# MAX96724_PINOUT.net
KiCad netlist of a schematic drawn in Altium Designer
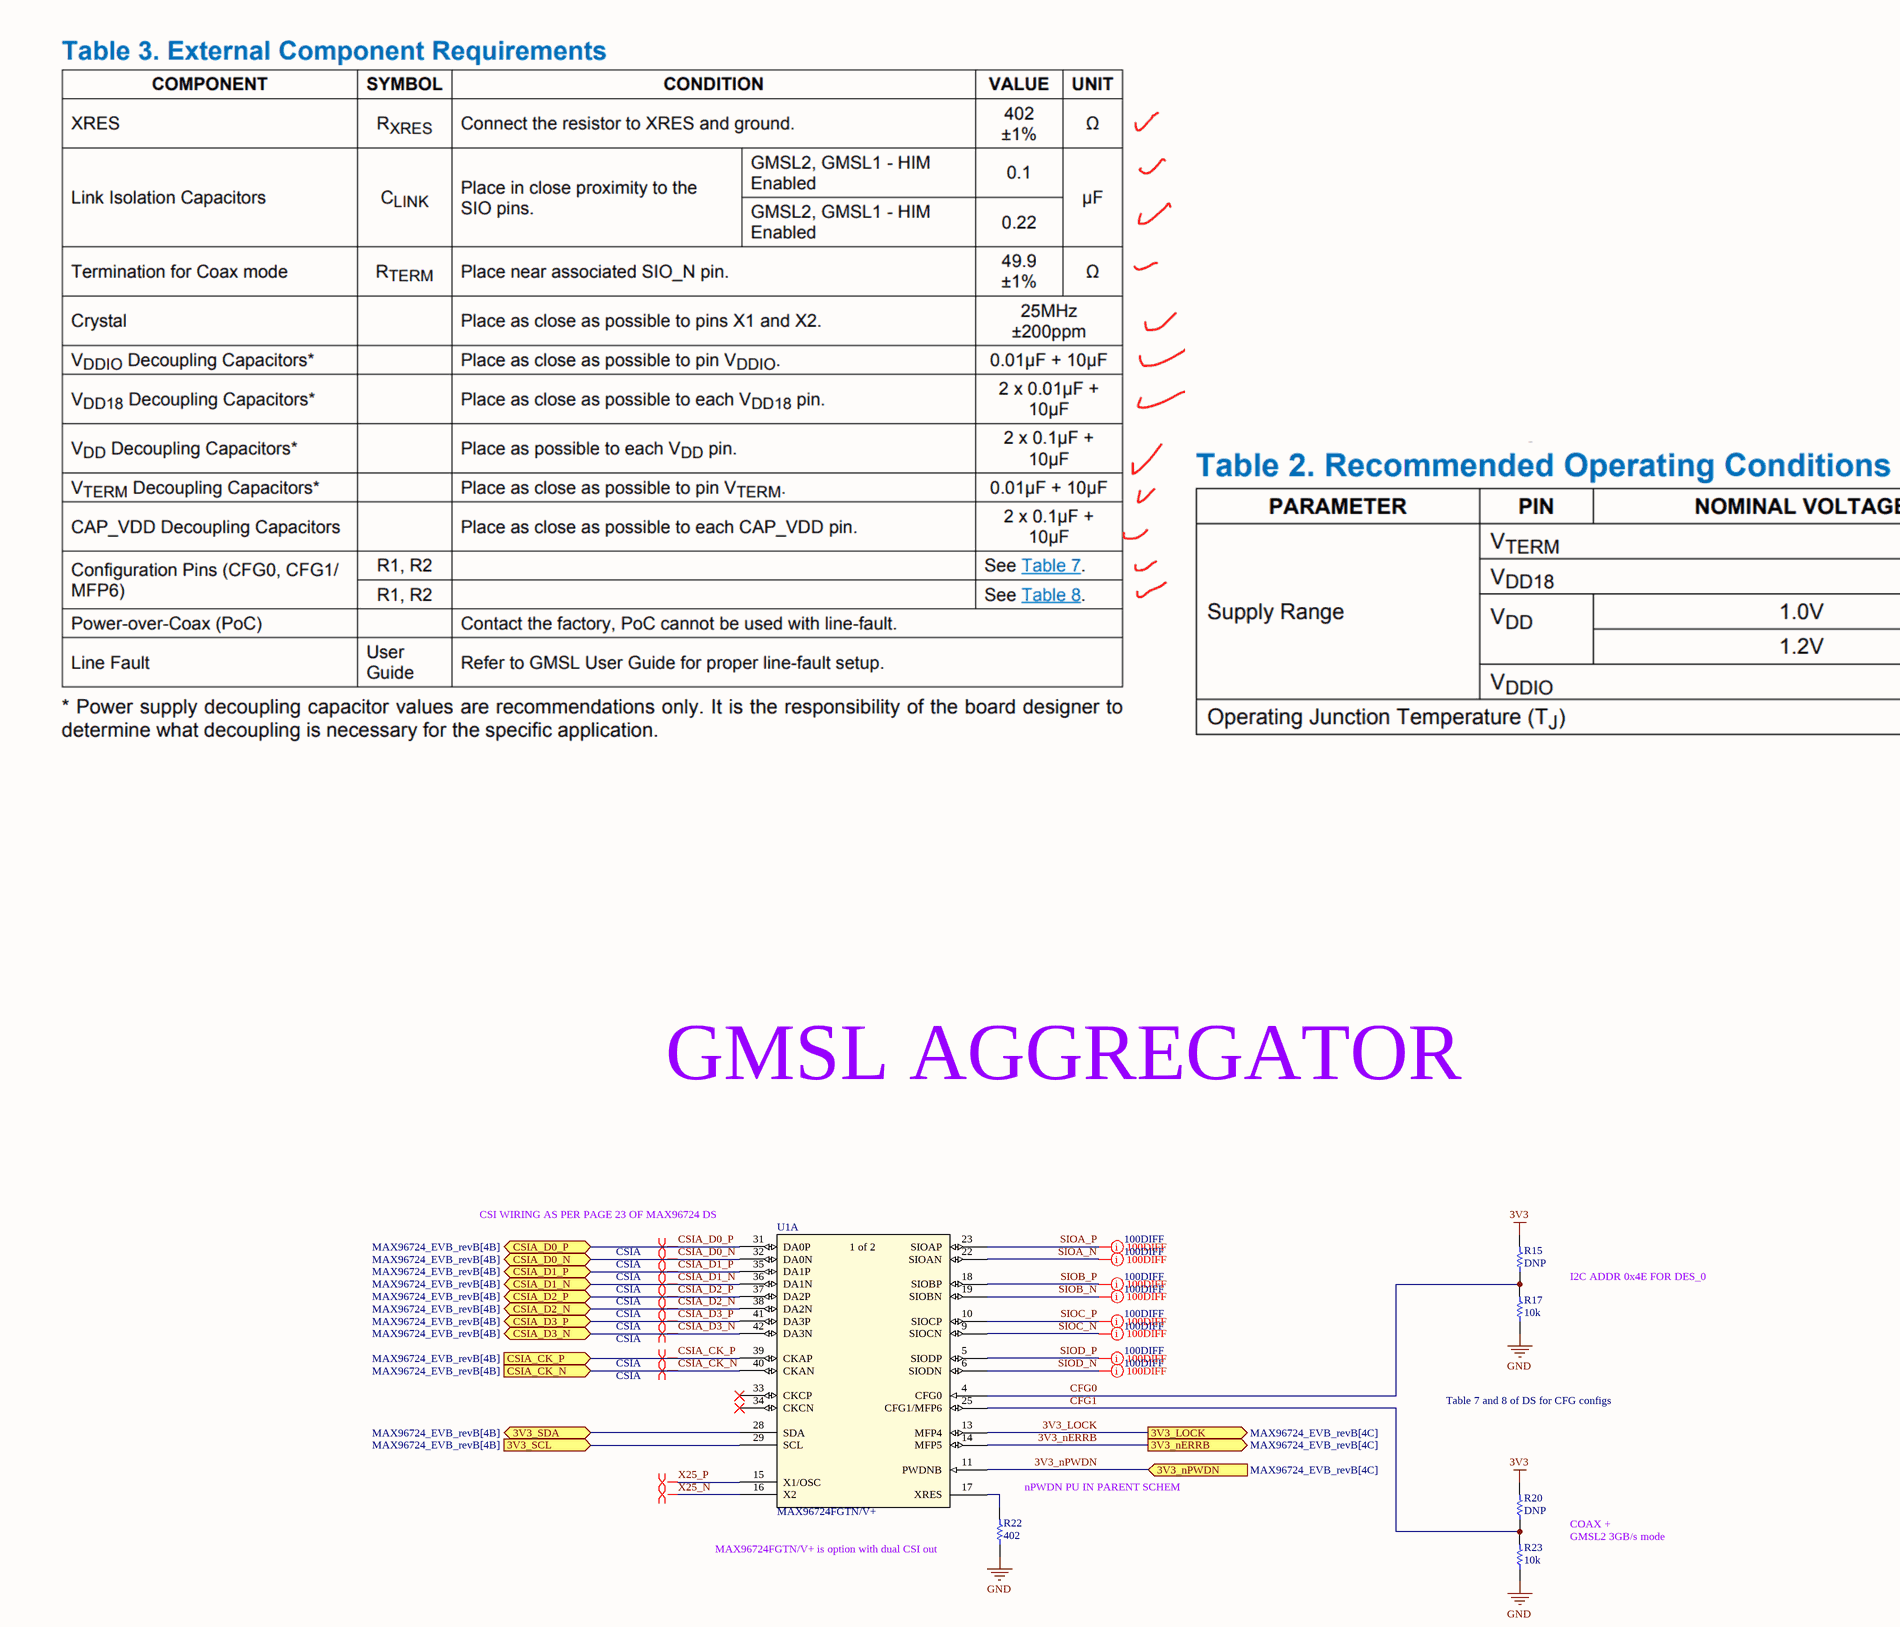
[diagram p0: MAX96724_PINOUT.SchDoc, top left]
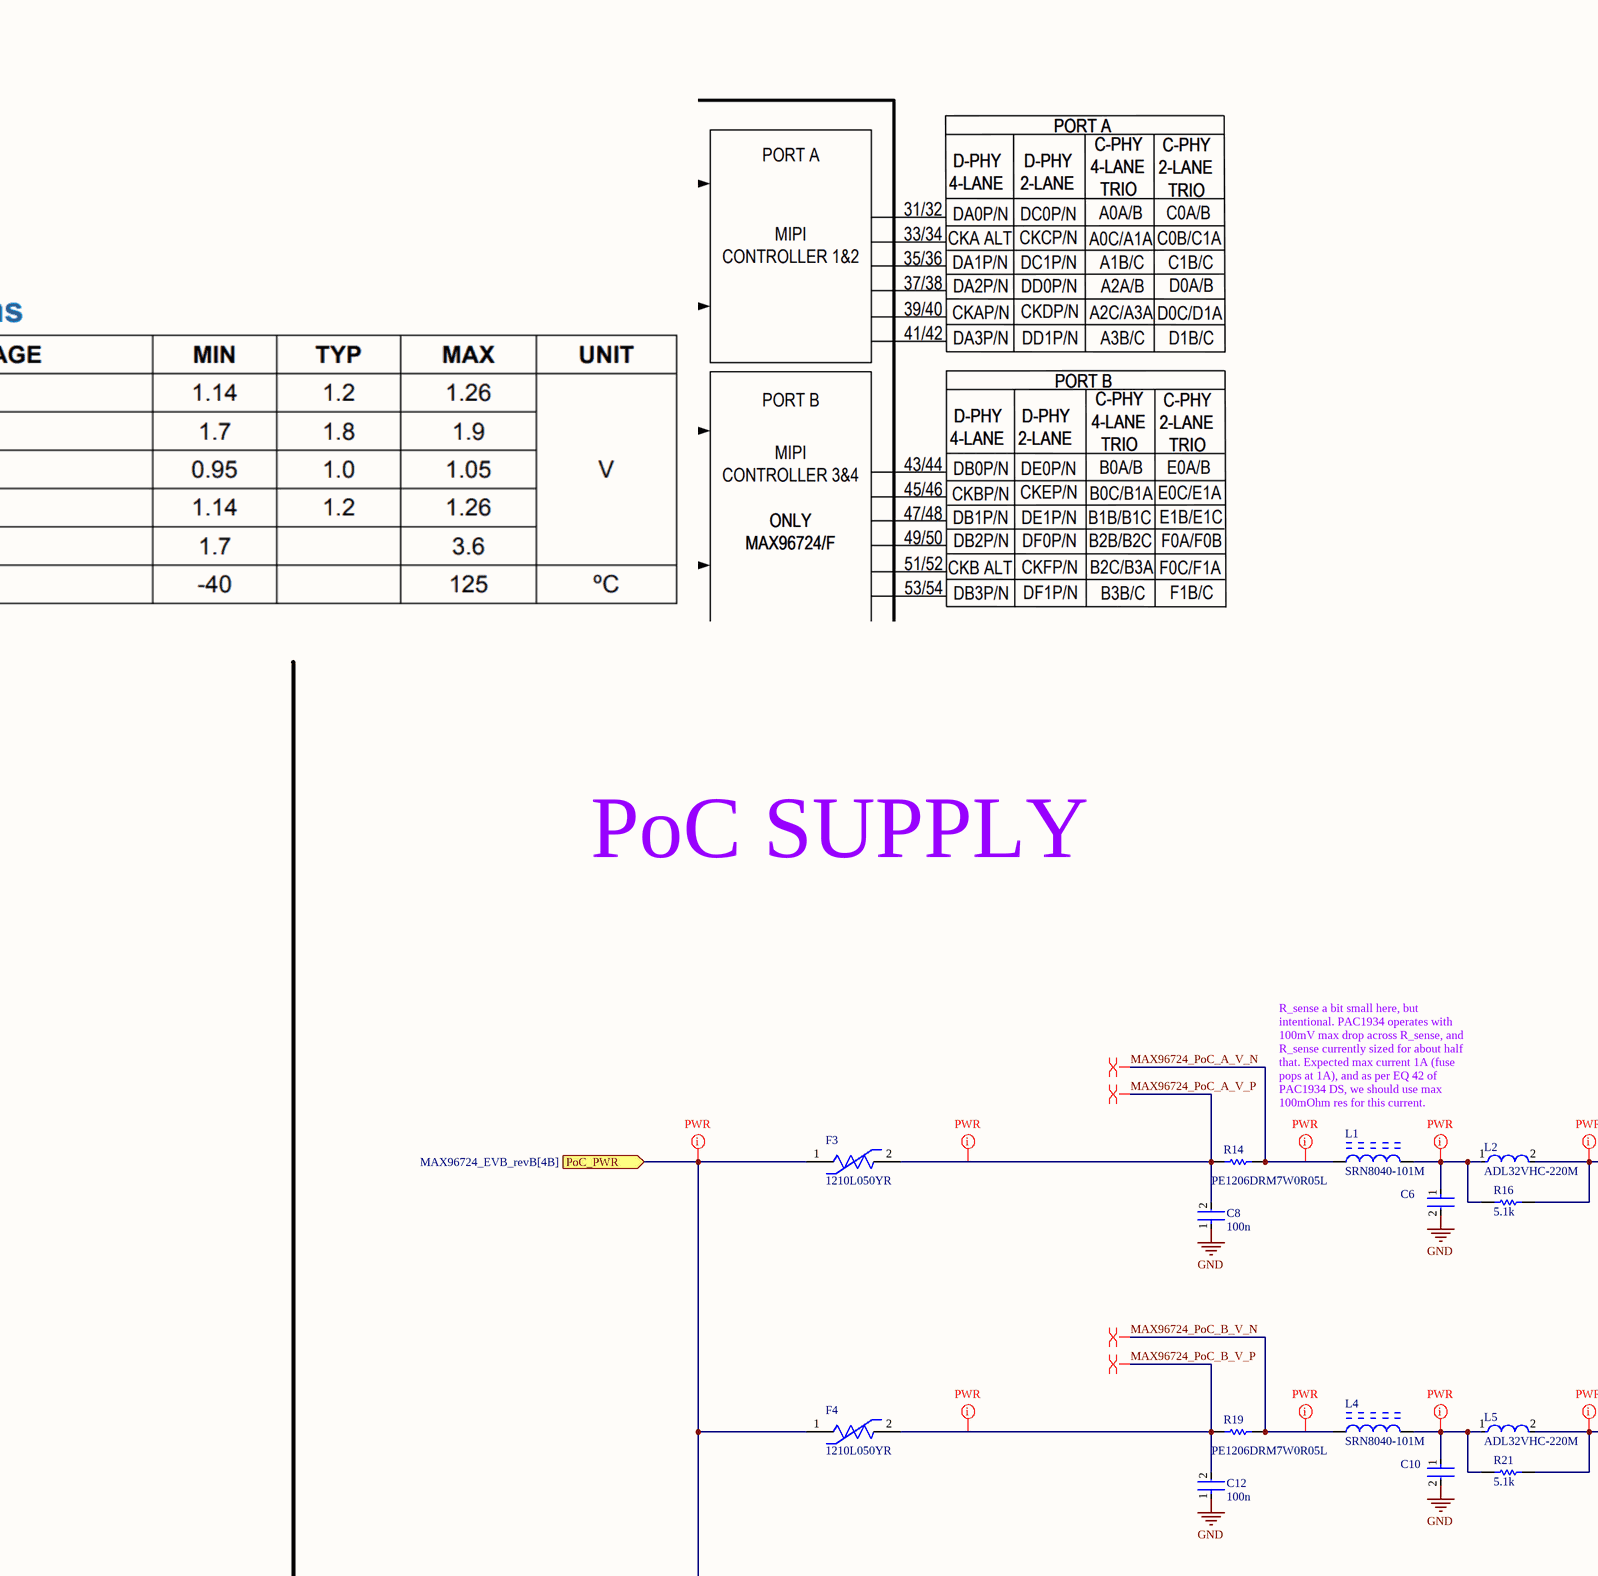
[diagram p1: MAX96724_PINOUT.SchDoc, top middle]
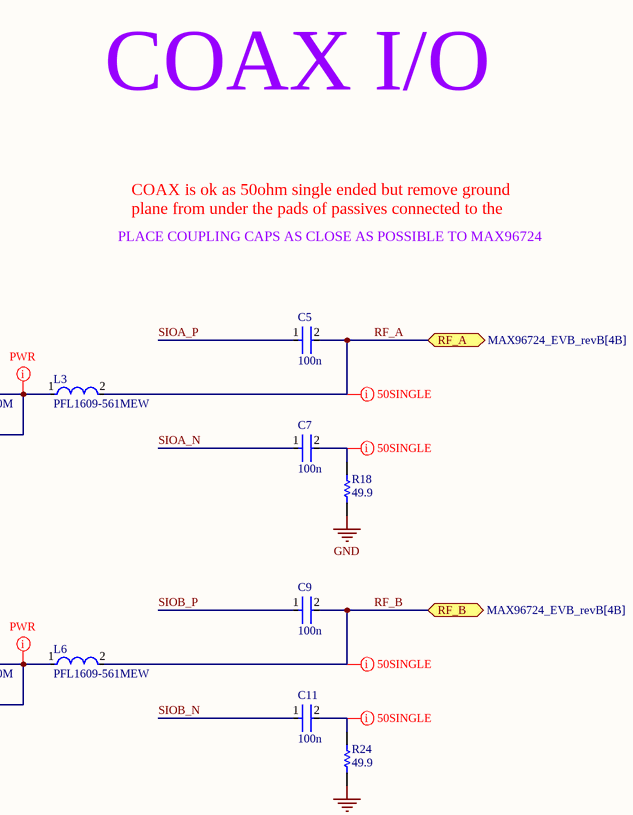
[diagram p2: MAX96724_PINOUT.SchDoc, top right]
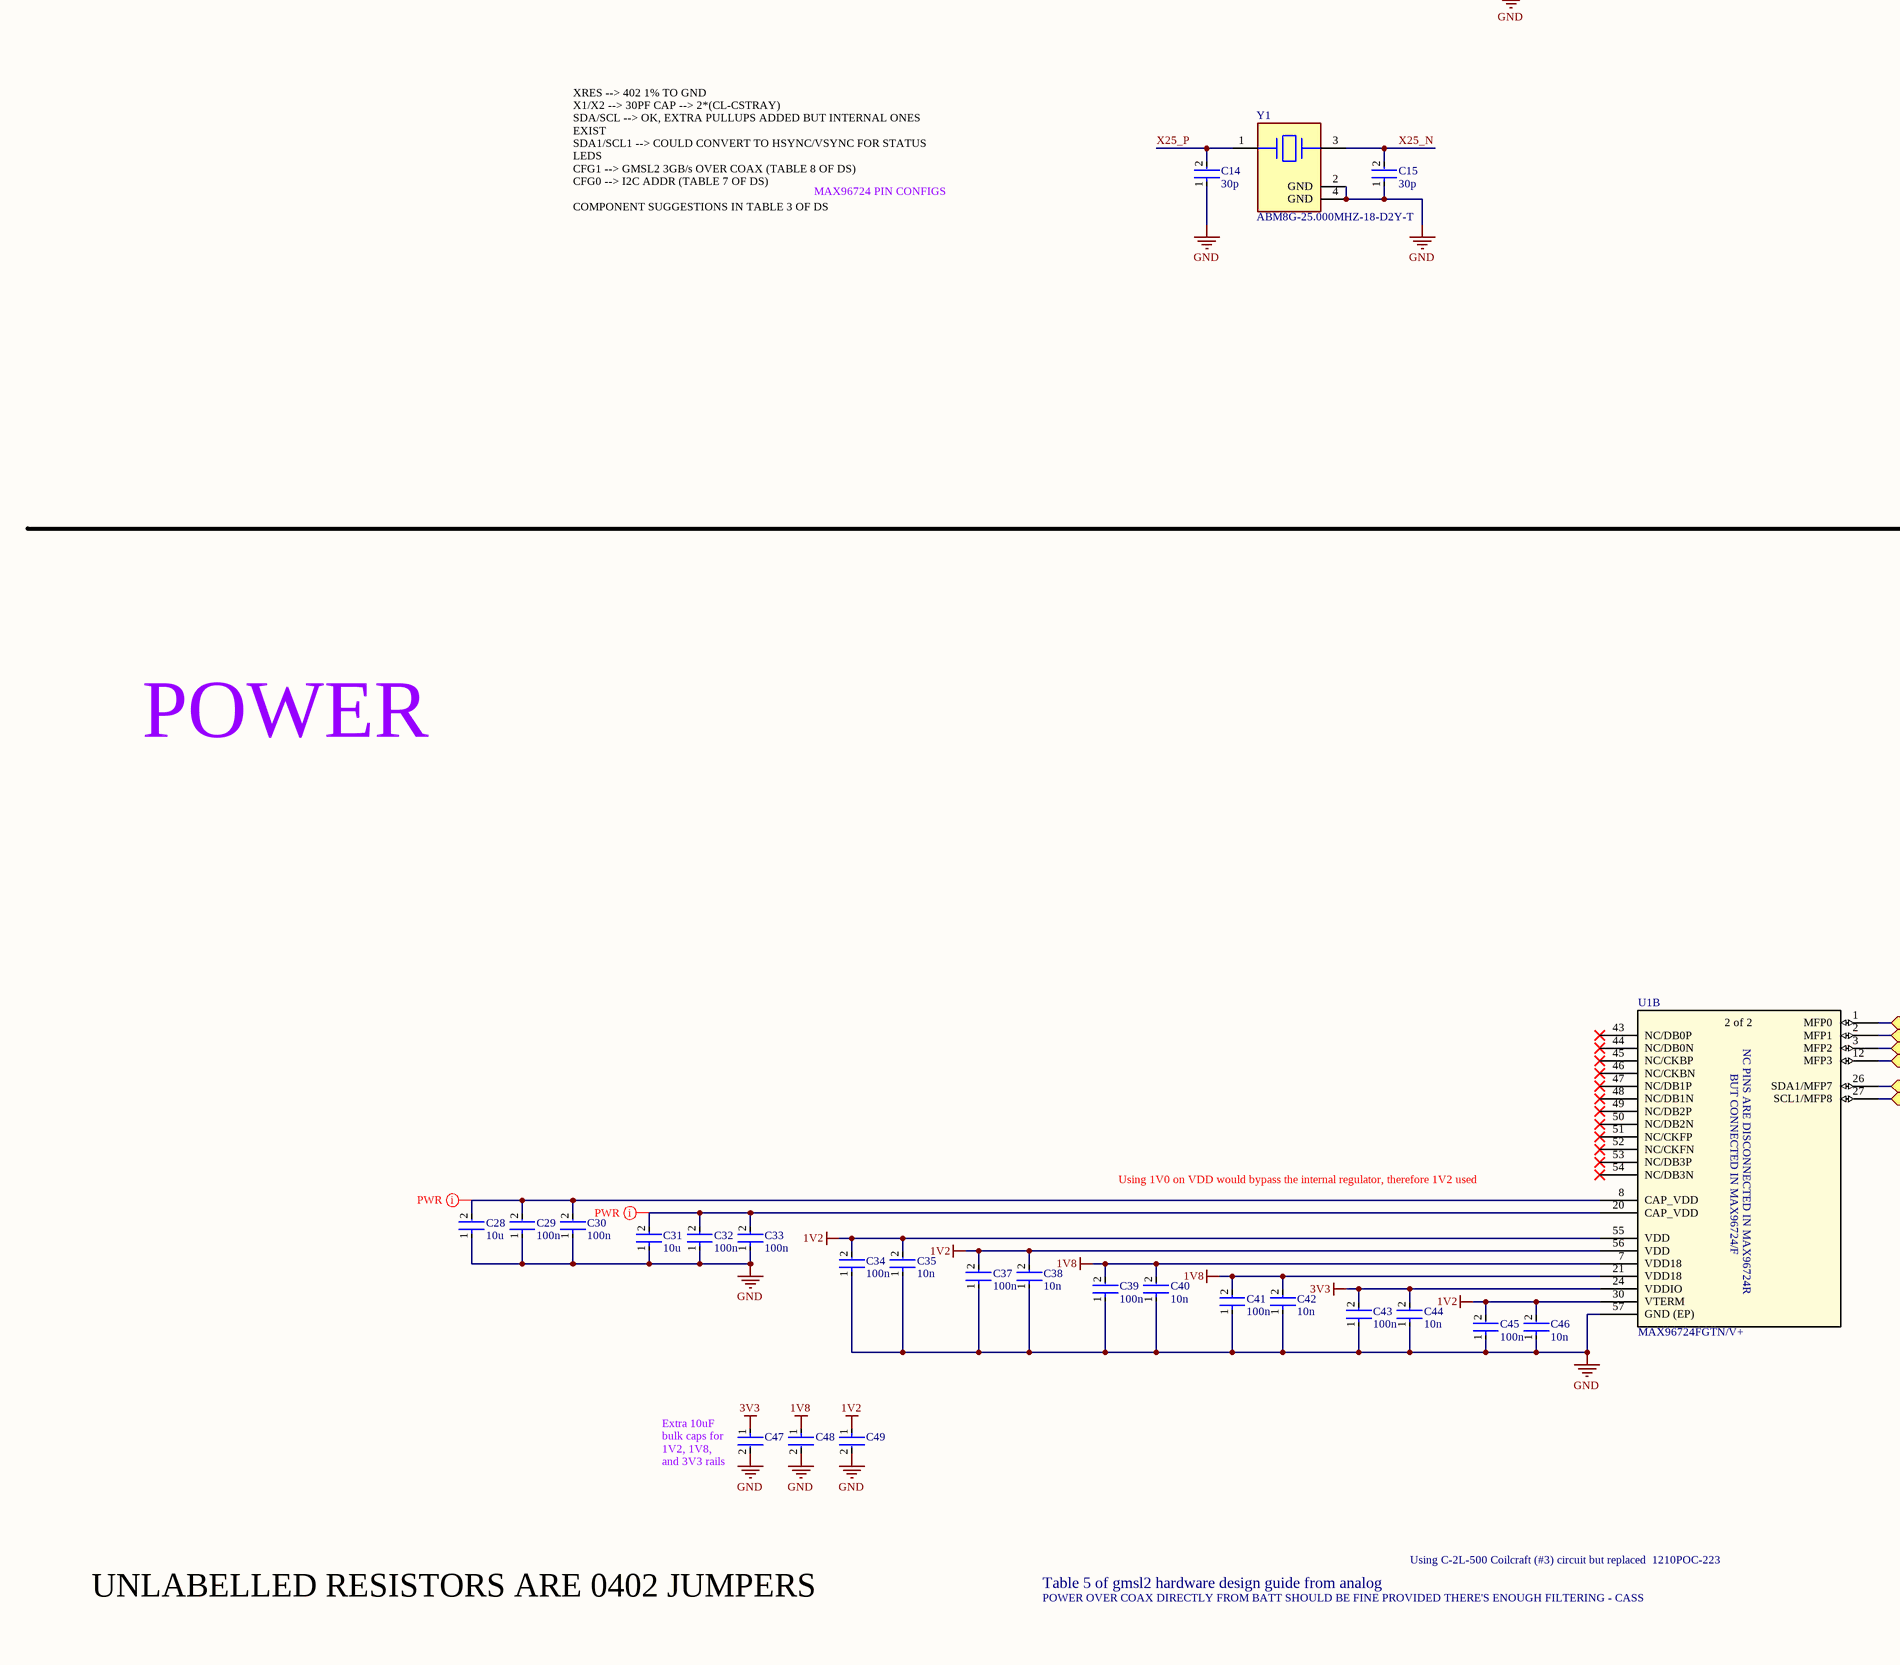
[diagram p3: MAX96724_PINOUT.SchDoc, bottom left]
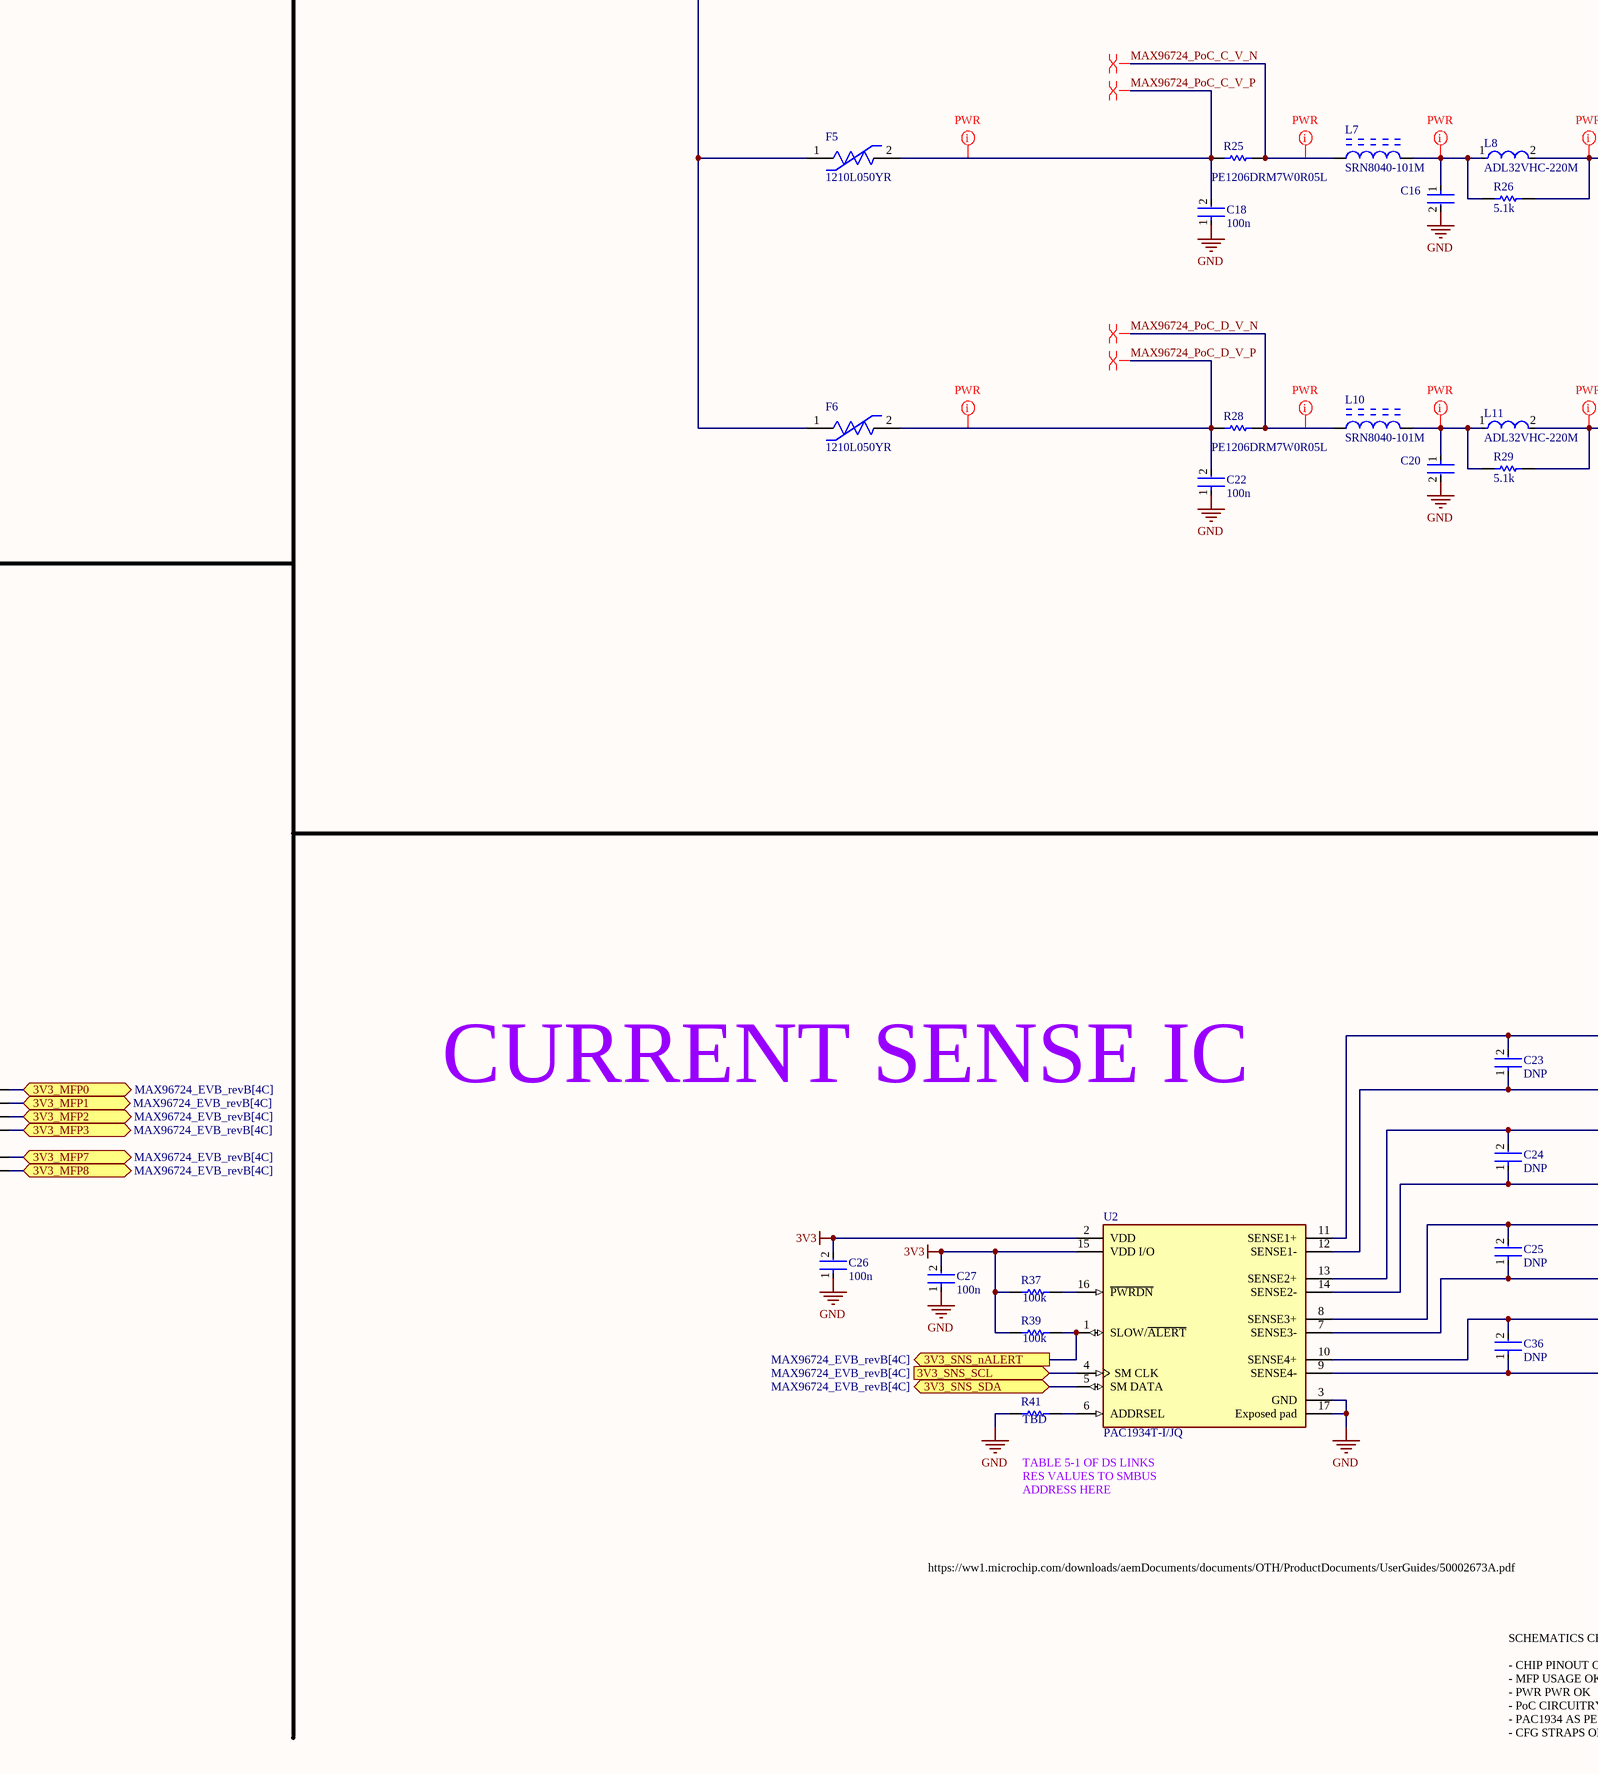
[diagram p4: MAX96724_PINOUT.SchDoc, bottom middle]
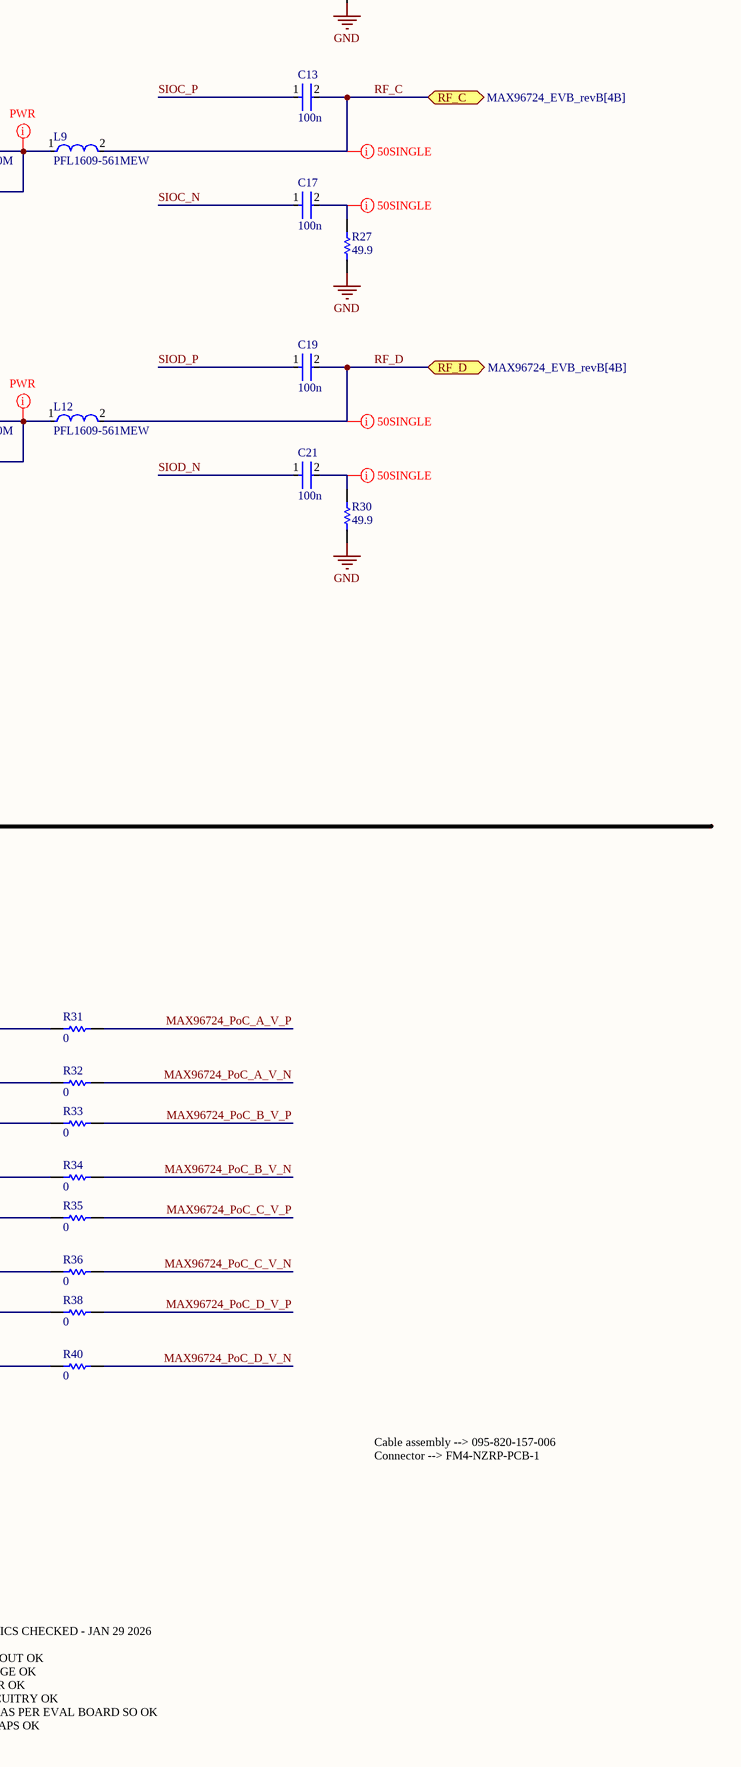
[diagram p5: MAX96724_PINOUT.SchDoc, bottom right]

(export (version "E")
  (design (tool "Eeschema 10.0.6"))
  (components
    (comp (ref "C5")
      (value "100n")
      (footprint "FP-0402-L_1_0_0_05-W_0_5-IPC_A")
      (description "LARGE PADS, 0402 CAP, CHANGE COMMENT TO MATCH REAL P/N")
      (libsource (lib "Space Concordia") (part "b4654b650e69147ec39a6b967a45e02"))
    )
    (comp (ref "C6")
      (value "GRM21BR61E226ME44L")
      (footprint "FP-GRM21B-0_2-e0_2_0_7-IPC_B")
      (description "Chip Multilayer Ceramic Capacitors for General Purpose, 0805, 22uF, X5R, 15%, 20%, 25V")
      (fields (field (name "TOLERANCE") "20%") (field (name "VOLTAGE") "25V"))
      (libsource (lib "Altium Content Vault") (part "b4654b650e69147ec39a6b967a45e02"))
    )
    (comp (ref "C7")
      (value "100n")
      (footprint "FP-0402-L_1_0_0_05-W_0_5-IPC_A")
      (description "LARGE PADS, 0402 CAP, CHANGE COMMENT TO MATCH REAL P/N")
      (libsource (lib "Space Concordia") (part "b4654b650e69147ec39a6b967a45e02"))
    )
    (comp (ref "C8")
      (value "100n")
      (footprint "FP-0402-L_1_0_0_05-W_0_5-IPC_A")
      (description "LARGE PADS, 0402 CAP, CHANGE COMMENT TO MATCH REAL P/N")
      (libsource (lib "Space Concordia") (part "b4654b650e69147ec39a6b967a45e02"))
    )
    (comp (ref "C9")
      (value "100n")
      (footprint "FP-0402-L_1_0_0_05-W_0_5-IPC_A")
      (description "LARGE PADS, 0402 CAP, CHANGE COMMENT TO MATCH REAL P/N")
      (libsource (lib "Space Concordia") (part "b4654b650e69147ec39a6b967a45e02"))
    )
    (comp (ref "C10")
      (value "GRM21BR61E226ME44L")
      (footprint "FP-GRM21B-0_2-e0_2_0_7-IPC_B")
      (description "Chip Multilayer Ceramic Capacitors for General Purpose, 0805, 22uF, X5R, 15%, 20%, 25V")
      (fields (field (name "TOLERANCE") "20%") (field (name "VOLTAGE") "25V"))
      (libsource (lib "Altium Content Vault") (part "b4654b650e69147ec39a6b967a45e02"))
    )
    (comp (ref "C11")
      (value "100n")
      (footprint "FP-0402-L_1_0_0_05-W_0_5-IPC_A")
      (description "LARGE PADS, 0402 CAP, CHANGE COMMENT TO MATCH REAL P/N")
      (libsource (lib "Space Concordia") (part "b4654b650e69147ec39a6b967a45e02"))
    )
    (comp (ref "C12")
      (value "100n")
      (footprint "FP-0402-L_1_0_0_05-W_0_5-IPC_A")
      (description "LARGE PADS, 0402 CAP, CHANGE COMMENT TO MATCH REAL P/N")
      (libsource (lib "Space Concordia") (part "b4654b650e69147ec39a6b967a45e02"))
    )
    (comp (ref "C13")
      (value "100n")
      (footprint "FP-0402-L_1_0_0_05-W_0_5-IPC_A")
      (description "LARGE PADS, 0402 CAP, CHANGE COMMENT TO MATCH REAL P/N")
      (libsource (lib "Space Concordia") (part "b4654b650e69147ec39a6b967a45e02"))
    )
    (comp (ref "C14")
      (value "30p")
      (footprint "FP-0402-L_1_0_0_05-W_0_5-IPC_A")
      (description "LARGE PADS, 0402 CAP, CHANGE COMMENT TO MATCH REAL P/N")
      (libsource (lib "Space Concordia") (part "b4654b650e69147ec39a6b967a45e02"))
    )
    (comp (ref "C15")
      (value "30p")
      (footprint "FP-0402-L_1_0_0_05-W_0_5-IPC_A")
      (description "LARGE PADS, 0402 CAP, CHANGE COMMENT TO MATCH REAL P/N")
      (libsource (lib "Space Concordia") (part "b4654b650e69147ec39a6b967a45e02"))
    )
    (comp (ref "C16")
      (value "GRM21BR61E226ME44L")
      (footprint "FP-GRM21B-0_2-e0_2_0_7-IPC_B")
      (description "Chip Multilayer Ceramic Capacitors for General Purpose, 0805, 22uF, X5R, 15%, 20%, 25V")
      (fields (field (name "TOLERANCE") "20%") (field (name "VOLTAGE") "25V"))
      (libsource (lib "Altium Content Vault") (part "b4654b650e69147ec39a6b967a45e02"))
    )
    (comp (ref "C17")
      (value "100n")
      (footprint "FP-0402-L_1_0_0_05-W_0_5-IPC_A")
      (description "LARGE PADS, 0402 CAP, CHANGE COMMENT TO MATCH REAL P/N")
      (libsource (lib "Space Concordia") (part "b4654b650e69147ec39a6b967a45e02"))
    )
    (comp (ref "C18")
      (value "100n")
      (footprint "FP-0402-L_1_0_0_05-W_0_5-IPC_A")
      (description "LARGE PADS, 0402 CAP, CHANGE COMMENT TO MATCH REAL P/N")
      (libsource (lib "Space Concordia") (part "b4654b650e69147ec39a6b967a45e02"))
    )
    (comp (ref "C19")
      (value "100n")
      (footprint "FP-0402-L_1_0_0_05-W_0_5-IPC_A")
      (description "LARGE PADS, 0402 CAP, CHANGE COMMENT TO MATCH REAL P/N")
      (libsource (lib "Space Concordia") (part "b4654b650e69147ec39a6b967a45e02"))
    )
    (comp (ref "C20")
      (value "GRM21BR61E226ME44L")
      (footprint "FP-GRM21B-0_2-e0_2_0_7-IPC_B")
      (description "Chip Multilayer Ceramic Capacitors for General Purpose, 0805, 22uF, X5R, 15%, 20%, 25V")
      (fields (field (name "TOLERANCE") "20%") (field (name "VOLTAGE") "25V"))
      (libsource (lib "Altium Content Vault") (part "b4654b650e69147ec39a6b967a45e02"))
    )
    (comp (ref "C21")
      (value "100n")
      (footprint "FP-0402-L_1_0_0_05-W_0_5-IPC_A")
      (description "LARGE PADS, 0402 CAP, CHANGE COMMENT TO MATCH REAL P/N")
      (libsource (lib "Space Concordia") (part "b4654b650e69147ec39a6b967a45e02"))
    )
    (comp (ref "C22")
      (value "100n")
      (footprint "FP-0402-L_1_0_0_05-W_0_5-IPC_A")
      (description "LARGE PADS, 0402 CAP, CHANGE COMMENT TO MATCH REAL P/N")
      (libsource (lib "Space Concordia") (part "b4654b650e69147ec39a6b967a45e02"))
    )
    (comp (ref "C23")
      (value "DNP")
      (footprint "FP-0402-L_1_0_0_05-W_0_5-IPC_A")
      (description "LARGE PADS, 0402 CAP, CHANGE COMMENT TO MATCH REAL P/N")
      (libsource (lib "Space Concordia") (part "b4654b650e69147ec39a6b967a45e02"))
    )
    (comp (ref "C24")
      (value "DNP")
      (footprint "FP-0402-L_1_0_0_05-W_0_5-IPC_A")
      (description "LARGE PADS, 0402 CAP, CHANGE COMMENT TO MATCH REAL P/N")
      (libsource (lib "Space Concordia") (part "b4654b650e69147ec39a6b967a45e02"))
    )
    (comp (ref "C25")
      (value "DNP")
      (footprint "FP-0402-L_1_0_0_05-W_0_5-IPC_A")
      (description "LARGE PADS, 0402 CAP, CHANGE COMMENT TO MATCH REAL P/N")
      (libsource (lib "Space Concordia") (part "b4654b650e69147ec39a6b967a45e02"))
    )
    (comp (ref "C26")
      (value "100n")
      (footprint "FP-0402-L_1_0_0_05-W_0_5-IPC_A")
      (description "LARGE PADS, 0402 CAP, CHANGE COMMENT TO MATCH REAL P/N")
      (libsource (lib "Space Concordia") (part "b4654b650e69147ec39a6b967a45e02"))
    )
    (comp (ref "C27")
      (value "100n")
      (footprint "FP-0402-L_1_0_0_05-W_0_5-IPC_A")
      (description "LARGE PADS, 0402 CAP, CHANGE COMMENT TO MATCH REAL P/N")
      (libsource (lib "Space Concordia") (part "b4654b650e69147ec39a6b967a45e02"))
    )
    (comp (ref "C28")
      (value "10u")
      (footprint "FP-0402-L_1_0_0_05-W_0_5-IPC_A")
      (description "LARGE PADS, 0402 CAP, CHANGE COMMENT TO MATCH REAL P/N")
      (libsource (lib "Space Concordia") (part "b4654b650e69147ec39a6b967a45e02"))
    )
    (comp (ref "C29")
      (value "100n")
      (footprint "FP-0402-L_1_0_0_05-W_0_5-IPC_A")
      (description "LARGE PADS, 0402 CAP, CHANGE COMMENT TO MATCH REAL P/N")
      (libsource (lib "Space Concordia") (part "b4654b650e69147ec39a6b967a45e02"))
    )
    (comp (ref "C30")
      (value "100n")
      (footprint "FP-0402-L_1_0_0_05-W_0_5-IPC_A")
      (description "LARGE PADS, 0402 CAP, CHANGE COMMENT TO MATCH REAL P/N")
      (libsource (lib "Space Concordia") (part "b4654b650e69147ec39a6b967a45e02"))
    )
    (comp (ref "C31")
      (value "10u")
      (footprint "FP-0402-L_1_0_0_05-W_0_5-IPC_A")
      (description "LARGE PADS, 0402 CAP, CHANGE COMMENT TO MATCH REAL P/N")
      (libsource (lib "Space Concordia") (part "b4654b650e69147ec39a6b967a45e02"))
    )
    (comp (ref "C32")
      (value "100n")
      (footprint "FP-0402-L_1_0_0_05-W_0_5-IPC_A")
      (description "LARGE PADS, 0402 CAP, CHANGE COMMENT TO MATCH REAL P/N")
      (libsource (lib "Space Concordia") (part "b4654b650e69147ec39a6b967a45e02"))
    )
    (comp (ref "C33")
      (value "100n")
      (footprint "FP-0402-L_1_0_0_05-W_0_5-IPC_A")
      (description "LARGE PADS, 0402 CAP, CHANGE COMMENT TO MATCH REAL P/N")
      (libsource (lib "Space Concordia") (part "b4654b650e69147ec39a6b967a45e02"))
    )
    (comp (ref "C34")
      (value "100n")
      (footprint "FP-0402-L_1_0_0_05-W_0_5-IPC_A")
      (description "LARGE PADS, 0402 CAP, CHANGE COMMENT TO MATCH REAL P/N")
      (libsource (lib "Space Concordia") (part "b4654b650e69147ec39a6b967a45e02"))
    )
    (comp (ref "C35")
      (value "10n")
      (footprint "FP-0402-L_1_0_0_05-W_0_5-IPC_A")
      (description "LARGE PADS, 0402 CAP, CHANGE COMMENT TO MATCH REAL P/N")
      (libsource (lib "Space Concordia") (part "b4654b650e69147ec39a6b967a45e02"))
    )
    (comp (ref "C36")
      (value "DNP")
      (footprint "FP-0402-L_1_0_0_05-W_0_5-IPC_A")
      (description "LARGE PADS, 0402 CAP, CHANGE COMMENT TO MATCH REAL P/N")
      (libsource (lib "Space Concordia") (part "b4654b650e69147ec39a6b967a45e02"))
    )
    (comp (ref "C37")
      (value "100n")
      (footprint "FP-0402-L_1_0_0_05-W_0_5-IPC_A")
      (description "LARGE PADS, 0402 CAP, CHANGE COMMENT TO MATCH REAL P/N")
      (libsource (lib "Space Concordia") (part "b4654b650e69147ec39a6b967a45e02"))
    )
    (comp (ref "C38")
      (value "10n")
      (footprint "FP-0402-L_1_0_0_05-W_0_5-IPC_A")
      (description "LARGE PADS, 0402 CAP, CHANGE COMMENT TO MATCH REAL P/N")
      (libsource (lib "Space Concordia") (part "b4654b650e69147ec39a6b967a45e02"))
    )
    (comp (ref "C39")
      (value "100n")
      (footprint "FP-0402-L_1_0_0_05-W_0_5-IPC_A")
      (description "LARGE PADS, 0402 CAP, CHANGE COMMENT TO MATCH REAL P/N")
      (libsource (lib "Space Concordia") (part "b4654b650e69147ec39a6b967a45e02"))
    )
    (comp (ref "C40")
      (value "10n")
      (footprint "FP-0402-L_1_0_0_05-W_0_5-IPC_A")
      (description "LARGE PADS, 0402 CAP, CHANGE COMMENT TO MATCH REAL P/N")
      (libsource (lib "Space Concordia") (part "b4654b650e69147ec39a6b967a45e02"))
    )
    (comp (ref "C41")
      (value "100n")
      (footprint "FP-0402-L_1_0_0_05-W_0_5-IPC_A")
      (description "LARGE PADS, 0402 CAP, CHANGE COMMENT TO MATCH REAL P/N")
      (libsource (lib "Space Concordia") (part "b4654b650e69147ec39a6b967a45e02"))
    )
    (comp (ref "C42")
      (value "10n")
      (footprint "FP-0402-L_1_0_0_05-W_0_5-IPC_A")
      (description "LARGE PADS, 0402 CAP, CHANGE COMMENT TO MATCH REAL P/N")
      (libsource (lib "Space Concordia") (part "b4654b650e69147ec39a6b967a45e02"))
    )
    (comp (ref "C43")
      (value "100n")
      (footprint "FP-0402-L_1_0_0_05-W_0_5-IPC_A")
      (description "LARGE PADS, 0402 CAP, CHANGE COMMENT TO MATCH REAL P/N")
      (libsource (lib "Space Concordia") (part "b4654b650e69147ec39a6b967a45e02"))
    )
    (comp (ref "C44")
      (value "10n")
      (footprint "FP-0402-L_1_0_0_05-W_0_5-IPC_A")
      (description "LARGE PADS, 0402 CAP, CHANGE COMMENT TO MATCH REAL P/N")
      (libsource (lib "Space Concordia") (part "b4654b650e69147ec39a6b967a45e02"))
    )
    (comp (ref "C45")
      (value "100n")
      (footprint "FP-0402-L_1_0_0_05-W_0_5-IPC_A")
      (description "LARGE PADS, 0402 CAP, CHANGE COMMENT TO MATCH REAL P/N")
      (libsource (lib "Space Concordia") (part "b4654b650e69147ec39a6b967a45e02"))
    )
    (comp (ref "C46")
      (value "10n")
      (footprint "FP-0402-L_1_0_0_05-W_0_5-IPC_A")
      (description "LARGE PADS, 0402 CAP, CHANGE COMMENT TO MATCH REAL P/N")
      (libsource (lib "Space Concordia") (part "b4654b650e69147ec39a6b967a45e02"))
    )
    (comp (ref "C47")
      (value "EMK107BBJ106MA-T")
      (footprint "FP-0603-L_1_6_0_2-W_0_8_0-MFG")
      (description "Multilayer Ceramic Capacitor 10uF 16V X5R 20% SMD 0603 T/R")
      (fields (field (name "TOLERANCE") "20%"))
      (libsource (lib "Altium Content Vault") (part "b4654b650e69147ec39a6b967a45e02"))
    )
    (comp (ref "C48")
      (value "EMK107BBJ106MA-T")
      (footprint "FP-0603-L_1_6_0_2-W_0_8_0-MFG")
      (description "Multilayer Ceramic Capacitor 10uF 16V X5R 20% SMD 0603 T/R")
      (fields (field (name "TOLERANCE") "20%"))
      (libsource (lib "Altium Content Vault") (part "b4654b650e69147ec39a6b967a45e02"))
    )
    (comp (ref "C49")
      (value "EMK107BBJ106MA-T")
      (footprint "FP-0603-L_1_6_0_2-W_0_8_0-MFG")
      (description "Multilayer Ceramic Capacitor 10uF 16V X5R 20% SMD 0603 T/R")
      (fields (field (name "TOLERANCE") "20%"))
      (libsource (lib "Altium Content Vault") (part "b4654b650e69147ec39a6b967a45e02"))
    )
    (comp (ref "F3")
      (value "1210L050YR")
      (footprint "FP-1210L050YR-MFG")
      (description "PTC RESET FUSE 13.2V 500MA 1210")
      (libsource (lib "Altium Content Vault") (part "fc31388045fc42ab786d6d00b506e9f"))
    )
    (comp (ref "F4")
      (value "1210L050YR")
      (footprint "FP-1210L050YR-MFG")
      (description "PTC RESET FUSE 13.2V 500MA 1210")
      (libsource (lib "Altium Content Vault") (part "fc31388045fc42ab786d6d00b506e9f"))
    )
    (comp (ref "F5")
      (value "1210L050YR")
      (footprint "FP-1210L050YR-MFG")
      (description "PTC RESET FUSE 13.2V 500MA 1210")
      (libsource (lib "Altium Content Vault") (part "fc31388045fc42ab786d6d00b506e9f"))
    )
    (comp (ref "F6")
      (value "1210L050YR")
      (footprint "FP-1210L050YR-MFG")
      (description "PTC RESET FUSE 13.2V 500MA 1210")
      (libsource (lib "Altium Content Vault") (part "fc31388045fc42ab786d6d00b506e9f"))
    )
    (comp (ref "L1")
      (value "SRN8040-101M")
      (footprint "BOUR-SRN8040-101M_V")
      (description "Semi-Shielded Power Inductor, 100 uH, -40 to 125 degC, 2-Pin SMD, RoHS, Tape and Reel")
      (fields (field (name "TOLERANCE") "±20\r\n\r\n%") (field (name "MANUFACTURER") "Bourns"))
      (libsource (lib "Altium Content Vault") (part "IND-FERR-2"))
    )
    (comp (ref "L2")
      (value "ADL32VHC-220M")
      (footprint "FP-1210POC-MFG")
      (description "NOT COILCRAFT - ACTUAL P# --> ADL32VHC-220M\r\n - Power Injection Chokes for PoC")
      (fields
        (field (name "MANUFACTURER") "coilcraft")
        (field (name "OCTOPART") "https://octopart.com/1210poc-223mrc-coilcraft-103207315")
      )
      (libsource (lib "Altium Content Vault") (part "725321dda6339637d4d059423bc1c3c"))
    )
    (comp (ref "L3")
      (value "PFL1609-561MEW")
      (footprint "FP-PFL1609-MFG")
      (description "Fixed Inductors PFL1609 Low Profile 0.56 uH 20 % 1.4 A")
      (fields (field (name "MANUFACTURER") "coilcraft") (field (name "TOLERANCE") "20%"))
      (libsource (lib "Altium Content Vault") (part "725321dda6339637d4d059423bc1c3c"))
    )
    (comp (ref "L4")
      (value "SRN8040-101M")
      (footprint "BOUR-SRN8040-101M_V")
      (description "Semi-Shielded Power Inductor, 100 uH, -40 to 125 degC, 2-Pin SMD, RoHS, Tape and Reel")
      (fields (field (name "TOLERANCE") "±20\r\n\r\n%") (field (name "MANUFACTURER") "Bourns"))
      (libsource (lib "Altium Content Vault") (part "IND-FERR-2"))
    )
    (comp (ref "L5")
      (value "ADL32VHC-220M")
      (footprint "FP-1210POC-MFG")
      (description "NOT COILCRAFT - ACTUAL P# --> ADL32VHC-220M\r\n - Power Injection Chokes for PoC")
      (fields
        (field (name "MANUFACTURER") "coilcraft")
        (field (name "OCTOPART") "https://octopart.com/1210poc-223mrc-coilcraft-103207315")
      )
      (libsource (lib "Altium Content Vault") (part "725321dda6339637d4d059423bc1c3c"))
    )
    (comp (ref "L6")
      (value "PFL1609-561MEW")
      (footprint "FP-PFL1609-MFG")
      (description "Fixed Inductors PFL1609 Low Profile 0.56 uH 20 % 1.4 A")
      (fields (field (name "MANUFACTURER") "coilcraft") (field (name "TOLERANCE") "20%"))
      (libsource (lib "Altium Content Vault") (part "725321dda6339637d4d059423bc1c3c"))
    )
    (comp (ref "L7")
      (value "SRN8040-101M")
      (footprint "BOUR-SRN8040-101M_V")
      (description "Semi-Shielded Power Inductor, 100 uH, -40 to 125 degC, 2-Pin SMD, RoHS, Tape and Reel")
      (fields (field (name "TOLERANCE") "±20\r\n\r\n%") (field (name "MANUFACTURER") "Bourns"))
      (libsource (lib "Altium Content Vault") (part "IND-FERR-2"))
    )
    (comp (ref "L8")
      (value "ADL32VHC-220M")
      (footprint "FP-1210POC-MFG")
      (description "NOT COILCRAFT - ACTUAL P# --> ADL32VHC-220M\r\n - Power Injection Chokes for PoC")
      (fields
        (field (name "MANUFACTURER") "coilcraft")
        (field (name "OCTOPART") "https://octopart.com/1210poc-223mrc-coilcraft-103207315")
      )
      (libsource (lib "Altium Content Vault") (part "725321dda6339637d4d059423bc1c3c"))
    )
    (comp (ref "L9")
      (value "PFL1609-561MEW")
      (footprint "FP-PFL1609-MFG")
      (description "Fixed Inductors PFL1609 Low Profile 0.56 uH 20 % 1.4 A")
      (fields (field (name "MANUFACTURER") "coilcraft") (field (name "TOLERANCE") "20%"))
      (libsource (lib "Altium Content Vault") (part "725321dda6339637d4d059423bc1c3c"))
    )
    (comp (ref "L10")
      (value "SRN8040-101M")
      (footprint "BOUR-SRN8040-101M_V")
      (description "Semi-Shielded Power Inductor, 100 uH, -40 to 125 degC, 2-Pin SMD, RoHS, Tape and Reel")
      (fields (field (name "TOLERANCE") "±20\r\n\r\n%") (field (name "MANUFACTURER") "Bourns"))
      (libsource (lib "Altium Content Vault") (part "IND-FERR-2"))
    )
    (comp (ref "L11")
      (value "ADL32VHC-220M")
      (footprint "FP-1210POC-MFG")
      (description "NOT COILCRAFT - ACTUAL P# --> ADL32VHC-220M\r\n - Power Injection Chokes for PoC")
      (fields
        (field (name "MANUFACTURER") "coilcraft")
        (field (name "OCTOPART") "https://octopart.com/1210poc-223mrc-coilcraft-103207315")
      )
      (libsource (lib "Altium Content Vault") (part "725321dda6339637d4d059423bc1c3c"))
    )
    (comp (ref "L12")
      (value "PFL1609-561MEW")
      (footprint "FP-PFL1609-MFG")
      (description "Fixed Inductors PFL1609 Low Profile 0.56 uH 20 % 1.4 A")
      (fields (field (name "MANUFACTURER") "coilcraft") (field (name "TOLERANCE") "20%"))
      (libsource (lib "Altium Content Vault") (part "725321dda6339637d4d059423bc1c3c"))
    )
    (comp (ref "R14")
      (value "PE1206DRM7W0R05L")
      (footprint "R1206B")
      (libsource (lib "Space Concordia") (part "Resistor"))
    )
    (comp (ref "R15")
      (value "DNP")
      (footprint "R0603B")
      (description "Resistor")
      (libsource (lib "Space Concordia") (part "Resistor"))
    )
    (comp (ref "R16")
      (value "5.1k")
      (footprint "R0603B")
      (description "Resistor")
      (libsource (lib "Space Concordia") (part "Resistor"))
    )
    (comp (ref "R17")
      (value "10k")
      (footprint "R0603B")
      (description "Resistor")
      (libsource (lib "Space Concordia") (part "Resistor"))
    )
    (comp (ref "R18")
      (value "49.9")
      (footprint "R0603B")
      (description "Resistor")
      (libsource (lib "Space Concordia") (part "Resistor"))
    )
    (comp (ref "R19")
      (value "PE1206DRM7W0R05L")
      (footprint "R1206B")
      (libsource (lib "Space Concordia") (part "Resistor"))
    )
    (comp (ref "R20")
      (value "DNP")
      (footprint "R0603B")
      (description "Resistor")
      (libsource (lib "Space Concordia") (part "Resistor"))
    )
    (comp (ref "R21")
      (value "5.1k")
      (footprint "R0603B")
      (description "Resistor")
      (libsource (lib "Space Concordia") (part "Resistor"))
    )
    (comp (ref "R22")
      (value "402")
      (footprint "R0603B")
      (description "Resistor")
      (libsource (lib "Space Concordia") (part "Resistor"))
    )
    (comp (ref "R23")
      (value "10k")
      (footprint "R0603B")
      (description "Resistor")
      (libsource (lib "Space Concordia") (part "Resistor"))
    )
    (comp (ref "R24")
      (value "49.9")
      (footprint "R0603B")
      (description "Resistor")
      (libsource (lib "Space Concordia") (part "Resistor"))
    )
    (comp (ref "R25")
      (value "PE1206DRM7W0R05L")
      (footprint "R1206B")
      (libsource (lib "Space Concordia") (part "Resistor"))
    )
    (comp (ref "R26")
      (value "5.1k")
      (footprint "R0603B")
      (description "Resistor")
      (libsource (lib "Space Concordia") (part "Resistor"))
    )
    (comp (ref "R27")
      (value "49.9")
      (footprint "R0603B")
      (description "Resistor")
      (libsource (lib "Space Concordia") (part "Resistor"))
    )
    (comp (ref "R28")
      (value "PE1206DRM7W0R05L")
      (footprint "R1206B")
      (libsource (lib "Space Concordia") (part "Resistor"))
    )
    (comp (ref "R29")
      (value "5.1k")
      (footprint "R0603B")
      (description "Resistor")
      (libsource (lib "Space Concordia") (part "Resistor"))
    )
    (comp (ref "R30")
      (value "49.9")
      (footprint "R0603B")
      (description "Resistor")
      (libsource (lib "Space Concordia") (part "Resistor"))
    )
    (comp (ref "R31")
      (value "0")
      (footprint "R0603B")
      (description "Resistor")
      (libsource (lib "Space Concordia") (part "Resistor"))
    )
    (comp (ref "R32")
      (value "0")
      (footprint "R0603B")
      (description "Resistor")
      (libsource (lib "Space Concordia") (part "Resistor"))
    )
    (comp (ref "R33")
      (value "0")
      (footprint "R0603B")
      (description "Resistor")
      (libsource (lib "Space Concordia") (part "Resistor"))
    )
    (comp (ref "R34")
      (value "0")
      (footprint "R0603B")
      (description "Resistor")
      (libsource (lib "Space Concordia") (part "Resistor"))
    )
    (comp (ref "R35")
      (value "0")
      (footprint "R0603B")
      (description "Resistor")
      (libsource (lib "Space Concordia") (part "Resistor"))
    )
    (comp (ref "R36")
      (value "0")
      (footprint "R0603B")
      (description "Resistor")
      (libsource (lib "Space Concordia") (part "Resistor"))
    )
    (comp (ref "R37")
      (value "100k")
      (footprint "R0603B")
      (description "Resistor")
      (libsource (lib "Space Concordia") (part "Resistor"))
    )
    (comp (ref "R38")
      (value "0")
      (footprint "R0603B")
      (description "Resistor")
      (libsource (lib "Space Concordia") (part "Resistor"))
    )
    (comp (ref "R39")
      (value "100k")
      (footprint "R0603B")
      (description "Resistor")
      (libsource (lib "Space Concordia") (part "Resistor"))
    )
    (comp (ref "R40")
      (value "0")
      (footprint "R0603B")
      (description "Resistor")
      (libsource (lib "Space Concordia") (part "Resistor"))
    )
    (comp (ref "R41")
      (value "TBD")
      (footprint "R0603B")
      (description "Resistor")
      (libsource (lib "Space Concordia") (part "Resistor"))
    )
    (comp (ref "U1")
      (value "MAX96724FGTN/V+")
      (footprint "MAX96724FGTN_V+-Footprint-1")
      (description "Quad Tunneling GMSL2/1 to CSI-2 Deserializer")
      (libsource (lib "Space Concordia") (part "MAX96724FGTN_V+-Symbol-1"))
    )
    (comp (ref "U2")
      (value "PAC1934T-I/JQ")
      (footprint "FP-C04-257-MFG")
      (description "QUAD HIGH-SIDE CURRENT SENSOR")
      (libsource (lib "Altium Content Vault") (part "528e103f3bb2621196c8a4997bef883"))
    )
    (comp (ref "Y1")
      (value "ABM8G-25.000MHZ-18-D2Y-T")
      (footprint "FP-ABM8G-MFG")
      (description "Crystal 25MHz ±20ppm (Tol) ±30ppm (Stability) 18pF FUND 60Ω 4-Pin SMD T/R")
      (fields (field (name "TOLERANCE") "20ppm"))
      (libsource (lib "Altium Content Vault") (part "48e526d86b7f2615d98721063c72f49"))
    )
  )
  (nets
    (net (code "1") (name "/3V3_LOCK") (class "Default")
      (node (ref "U1") (pin "13") (pinfunction "MFP4_13") (pintype "bidirectional"))
    )
    (net (code "2") (name "/3V3_MFP0") (class "Default")
      (node (ref "U1") (pin "1") (pinfunction "MFP0_1") (pintype "bidirectional"))
    )
    (net (code "3") (name "/3V3_MFP1") (class "Default")
      (node (ref "U1") (pin "2") (pinfunction "MFP1_2") (pintype "bidirectional"))
    )
    (net (code "4") (name "/3V3_MFP2") (class "Default")
      (node (ref "U1") (pin "3") (pinfunction "MFP2_3") (pintype "bidirectional"))
    )
    (net (code "5") (name "/3V3_MFP3") (class "Default")
      (node (ref "U1") (pin "12") (pinfunction "MFP3_12") (pintype "bidirectional"))
    )
    (net (code "6") (name "/3V3_MFP7") (class "Default")
      (node (ref "U1") (pin "26") (pinfunction "SDA1/MFP7_26") (pintype "bidirectional"))
    )
    (net (code "7") (name "/3V3_MFP8") (class "Default")
      (node (ref "U1") (pin "27") (pinfunction "SCL1/MFP8_27") (pintype "bidirectional"))
    )
    (net (code "8") (name "/3V3_SCL") (class "Default")
      (node (ref "U1") (pin "29") (pinfunction "SCL_29") (pintype "passive"))
    )
    (net (code "9") (name "/3V3_SDA") (class "Default")
      (node (ref "U1") (pin "28") (pinfunction "SDA_28") (pintype "passive"))
    )
    (net (code "10") (name "/3V3_SNS_SCL") (class "Default")
      (node (ref "U2") (pin "4") (pinfunction "SM_CLK_4") (pintype "input"))
    )
    (net (code "11") (name "/3V3_SNS_SDA") (class "Default")
      (node (ref "U2") (pin "5") (pinfunction "SM_DATA_5") (pintype "bidirectional"))
    )
    (net (code "12") (name "/3V3_SNS_nALERT") (class "Default")
      (node (ref "R39") (pin "1") (pinfunction "1_1") (pintype "passive"))
      (node (ref "U2") (pin "1") (pinfunction "SLOW/~{ALERT}_1") (pintype "bidirectional"))
    )
    (net (code "13") (name "/3V3_nERRB") (class "Default")
      (node (ref "U1") (pin "14") (pinfunction "MFP5_14") (pintype "bidirectional"))
    )
    (net (code "14") (name "/3V3_nPWDN") (class "Default")
      (node (ref "U1") (pin "11") (pinfunction "PWDNB_11") (pintype "input"))
    )
    (net (code "15") (name "/CFG0") (class "Default")
      (node (ref "R15") (pin "1") (pinfunction "1_1") (pintype "passive"))
      (node (ref "R17") (pin "2") (pinfunction "2_2") (pintype "passive"))
      (node (ref "U1") (pin "4") (pinfunction "CFG0_4") (pintype "input"))
    )
    (net (code "16") (name "/CFG1") (class "Default")
      (node (ref "R20") (pin "1") (pinfunction "1_1") (pintype "passive"))
      (node (ref "R23") (pin "2") (pinfunction "2_2") (pintype "passive"))
      (node (ref "U1") (pin "25") (pinfunction "CFG1/MFP6_25") (pintype "bidirectional"))
    )
    (net (code "17") (name "/CSIA_CK_N") (class "Default")
      (node (ref "U1") (pin "40") (pinfunction "CKAN_40") (pintype "bidirectional"))
    )
    (net (code "18") (name "/CSIA_CK_P") (class "Default")
      (node (ref "U1") (pin "39") (pinfunction "CKAP_39") (pintype "bidirectional"))
    )
    (net (code "19") (name "/CSIA_D0_N") (class "Default")
      (node (ref "U1") (pin "32") (pinfunction "DA0N_32") (pintype "bidirectional"))
    )
    (net (code "20") (name "/CSIA_D0_P") (class "Default")
      (node (ref "U1") (pin "31") (pinfunction "DA0P_31") (pintype "bidirectional"))
    )
    (net (code "21") (name "/CSIA_D1_N") (class "Default")
      (node (ref "U1") (pin "36") (pinfunction "DA1N_36") (pintype "bidirectional"))
    )
    (net (code "22") (name "/CSIA_D1_P") (class "Default")
      (node (ref "U1") (pin "35") (pinfunction "DA1P_35") (pintype "bidirectional"))
    )
    (net (code "23") (name "/CSIA_D2_N") (class "Default")
      (node (ref "U1") (pin "38") (pinfunction "DA2N_38") (pintype "bidirectional"))
    )
    (net (code "24") (name "/CSIA_D2_P") (class "Default")
      (node (ref "U1") (pin "37") (pinfunction "DA2P_37") (pintype "bidirectional"))
    )
    (net (code "25") (name "/CSIA_D3_N") (class "Default")
      (node (ref "U1") (pin "42") (pinfunction "DA3N_42") (pintype "bidirectional"))
    )
    (net (code "26") (name "/CSIA_D3_P") (class "Default")
      (node (ref "U1") (pin "41") (pinfunction "DA3P_41") (pintype "bidirectional"))
    )
    (net (code "27") (name "/MAX96724_PoC_A_V_N") (class "Default")
      (node (ref "L1") (pin "1") (pinfunction "1_1") (pintype "passive"))
      (node (ref "R14") (pin "1") (pinfunction "1_1") (pintype "passive"))
      (node (ref "R32") (pin "1") (pinfunction "1_1") (pintype "passive"))
    )
    (net (code "28") (name "/MAX96724_PoC_A_V_P") (class "Default")
      (node (ref "C8") (pin "2") (pinfunction "2_2") (pintype "passive"))
      (node (ref "F3") (pin "2") (pinfunction "2_2") (pintype "passive"))
      (node (ref "R14") (pin "2") (pinfunction "2_2") (pintype "passive"))
      (node (ref "R31") (pin "1") (pinfunction "1_1") (pintype "passive"))
    )
    (net (code "29") (name "/MAX96724_PoC_B_V_N") (class "Default")
      (node (ref "L4") (pin "1") (pinfunction "1_1") (pintype "passive"))
      (node (ref "R19") (pin "1") (pinfunction "1_1") (pintype "passive"))
      (node (ref "R34") (pin "1") (pinfunction "1_1") (pintype "passive"))
    )
    (net (code "30") (name "/MAX96724_PoC_B_V_P") (class "Default")
      (node (ref "C12") (pin "2") (pinfunction "2_2") (pintype "passive"))
      (node (ref "F4") (pin "2") (pinfunction "2_2") (pintype "passive"))
      (node (ref "R19") (pin "2") (pinfunction "2_2") (pintype "passive"))
      (node (ref "R33") (pin "1") (pinfunction "1_1") (pintype "passive"))
    )
    (net (code "31") (name "/MAX96724_PoC_C_V_N") (class "Default")
      (node (ref "L7") (pin "1") (pinfunction "1_1") (pintype "passive"))
      (node (ref "R25") (pin "1") (pinfunction "1_1") (pintype "passive"))
      (node (ref "R36") (pin "1") (pinfunction "1_1") (pintype "passive"))
    )
    (net (code "32") (name "/MAX96724_PoC_C_V_P") (class "Default")
      (node (ref "C18") (pin "2") (pinfunction "2_2") (pintype "passive"))
      (node (ref "F5") (pin "2") (pinfunction "2_2") (pintype "passive"))
      (node (ref "R25") (pin "2") (pinfunction "2_2") (pintype "passive"))
      (node (ref "R35") (pin "1") (pinfunction "1_1") (pintype "passive"))
    )
    (net (code "33") (name "/MAX96724_PoC_D_V_N") (class "Default")
      (node (ref "L10") (pin "1") (pinfunction "1_1") (pintype "passive"))
      (node (ref "R28") (pin "1") (pinfunction "1_1") (pintype "passive"))
      (node (ref "R40") (pin "1") (pinfunction "1_1") (pintype "passive"))
    )
    (net (code "34") (name "/MAX96724_PoC_D_V_P") (class "Default")
      (node (ref "C22") (pin "2") (pinfunction "2_2") (pintype "passive"))
      (node (ref "F6") (pin "2") (pinfunction "2_2") (pintype "passive"))
      (node (ref "R28") (pin "2") (pinfunction "2_2") (pintype "passive"))
      (node (ref "R38") (pin "1") (pinfunction "1_1") (pintype "passive"))
    )
    (net (code "35") (name "/PoC_PWR") (class "Default")
      (node (ref "F3") (pin "1") (pinfunction "1_1") (pintype "passive"))
      (node (ref "F4") (pin "1") (pinfunction "1_1") (pintype "passive"))
      (node (ref "F5") (pin "1") (pinfunction "1_1") (pintype "passive"))
      (node (ref "F6") (pin "1") (pinfunction "1_1") (pintype "passive"))
    )
    (net (code "36") (name "/RF_A") (class "Default")
      (node (ref "C5") (pin "2") (pinfunction "2_2") (pintype "passive"))
      (node (ref "L3") (pin "2") (pinfunction "2_2") (pintype "passive"))
    )
    (net (code "37") (name "/RF_B") (class "Default")
      (node (ref "C9") (pin "2") (pinfunction "2_2") (pintype "passive"))
      (node (ref "L6") (pin "2") (pinfunction "2_2") (pintype "passive"))
    )
    (net (code "38") (name "/RF_C") (class "Default")
      (node (ref "C13") (pin "2") (pinfunction "2_2") (pintype "passive"))
      (node (ref "L9") (pin "2") (pinfunction "2_2") (pintype "passive"))
    )
    (net (code "39") (name "/RF_D") (class "Default")
      (node (ref "C19") (pin "2") (pinfunction "2_2") (pintype "passive"))
      (node (ref "L12") (pin "2") (pinfunction "2_2") (pintype "passive"))
    )
    (net (code "40") (name "/SIOA_N") (class "Default")
      (node (ref "C7") (pin "1") (pinfunction "1_1") (pintype "passive"))
      (node (ref "U1") (pin "22") (pinfunction "SIOAN_22") (pintype "bidirectional"))
    )
    (net (code "41") (name "/SIOA_P") (class "Default")
      (node (ref "C5") (pin "1") (pinfunction "1_1") (pintype "passive"))
      (node (ref "U1") (pin "23") (pinfunction "SIOAP_23") (pintype "bidirectional"))
    )
    (net (code "42") (name "/SIOB_N") (class "Default")
      (node (ref "C11") (pin "1") (pinfunction "1_1") (pintype "passive"))
      (node (ref "U1") (pin "19") (pinfunction "SIOBN_19") (pintype "bidirectional"))
    )
    (net (code "43") (name "/SIOB_P") (class "Default")
      (node (ref "C9") (pin "1") (pinfunction "1_1") (pintype "passive"))
      (node (ref "U1") (pin "18") (pinfunction "SIOBP_18") (pintype "bidirectional"))
    )
    (net (code "44") (name "/SIOC_N") (class "Default")
      (node (ref "C17") (pin "1") (pinfunction "1_1") (pintype "passive"))
      (node (ref "U1") (pin "9") (pinfunction "SIOCN_9") (pintype "bidirectional"))
    )
    (net (code "45") (name "/SIOC_P") (class "Default")
      (node (ref "C13") (pin "1") (pinfunction "1_1") (pintype "passive"))
      (node (ref "U1") (pin "10") (pinfunction "SIOCP_10") (pintype "bidirectional"))
    )
    (net (code "46") (name "/SIOD_N") (class "Default")
      (node (ref "C21") (pin "1") (pinfunction "1_1") (pintype "passive"))
      (node (ref "U1") (pin "6") (pinfunction "SIODN_6") (pintype "bidirectional"))
    )
    (net (code "47") (name "/SIOD_P") (class "Default")
      (node (ref "C19") (pin "1") (pinfunction "1_1") (pintype "passive"))
      (node (ref "U1") (pin "5") (pinfunction "SIODP_5") (pintype "bidirectional"))
    )
    (net (code "48") (name "/X25_N") (class "Default")
      (node (ref "C15") (pin "2") (pinfunction "2_2") (pintype "passive"))
      (node (ref "U1") (pin "16") (pinfunction "X2_16") (pintype "passive"))
      (node (ref "Y1") (pin "3") (pinfunction "3_3") (pintype "passive"))
    )
    (net (code "49") (name "/X25_P") (class "Default")
      (node (ref "C14") (pin "2") (pinfunction "2_2") (pintype "passive"))
      (node (ref "U1") (pin "15") (pinfunction "X1/OSC_15") (pintype "passive"))
      (node (ref "Y1") (pin "1") (pinfunction "1_1") (pintype "passive"))
    )
    (net (code "50") (name "1V2") (class "Default")
      (node (ref "C34") (pin "2") (pinfunction "2_2") (pintype "passive"))
      (node (ref "C35") (pin "2") (pinfunction "2_2") (pintype "passive"))
      (node (ref "C37") (pin "2") (pinfunction "2_2") (pintype "passive"))
      (node (ref "C38") (pin "2") (pinfunction "2_2") (pintype "passive"))
      (node (ref "C45") (pin "2") (pinfunction "2_2") (pintype "passive"))
      (node (ref "C46") (pin "2") (pinfunction "2_2") (pintype "passive"))
      (node (ref "C49") (pin "1") (pinfunction "1_1") (pintype "passive"))
      (node (ref "U1") (pin "30") (pinfunction "VTERM_30") (pintype "power_in"))
      (node (ref "U1") (pin "55") (pinfunction "VDD_55") (pintype "power_in"))
      (node (ref "U1") (pin "56") (pinfunction "VDD_56") (pintype "power_in"))
    )
    (net (code "51") (name "1V8") (class "Default")
      (node (ref "C39") (pin "2") (pinfunction "2_2") (pintype "passive"))
      (node (ref "C40") (pin "2") (pinfunction "2_2") (pintype "passive"))
      (node (ref "C41") (pin "2") (pinfunction "2_2") (pintype "passive"))
      (node (ref "C42") (pin "2") (pinfunction "2_2") (pintype "passive"))
      (node (ref "C48") (pin "1") (pinfunction "1_1") (pintype "passive"))
      (node (ref "U1") (pin "21") (pinfunction "VDD18_21") (pintype "power_in"))
      (node (ref "U1") (pin "7") (pinfunction "VDD18_7") (pintype "power_in"))
    )
    (net (code "52") (name "3V3") (class "Default")
      (node (ref "C26") (pin "2") (pinfunction "2_2") (pintype "passive"))
      (node (ref "C27") (pin "2") (pinfunction "2_2") (pintype "passive"))
      (node (ref "C43") (pin "2") (pinfunction "2_2") (pintype "passive"))
      (node (ref "C44") (pin "2") (pinfunction "2_2") (pintype "passive"))
      (node (ref "C47") (pin "1") (pinfunction "1_1") (pintype "passive"))
      (node (ref "R15") (pin "2") (pinfunction "2_2") (pintype "passive"))
      (node (ref "R20") (pin "2") (pinfunction "2_2") (pintype "passive"))
      (node (ref "R37") (pin "2") (pinfunction "2_2") (pintype "passive"))
      (node (ref "R39") (pin "2") (pinfunction "2_2") (pintype "passive"))
      (node (ref "U1") (pin "24") (pinfunction "VDDIO_24") (pintype "power_in"))
      (node (ref "U2") (pin "15") (pinfunction "VDD_I/O_15") (pintype "power_in"))
      (node (ref "U2") (pin "2") (pinfunction "VDD_2") (pintype "power_in"))
    )
    (net (code "53") (name "GND") (class "Default")
      (node (ref "C10") (pin "2") (pinfunction "2_2") (pintype "passive"))
      (node (ref "C12") (pin "1") (pinfunction "1_1") (pintype "passive"))
      (node (ref "C14") (pin "1") (pinfunction "1_1") (pintype "passive"))
      (node (ref "C15") (pin "1") (pinfunction "1_1") (pintype "passive"))
      (node (ref "C16") (pin "2") (pinfunction "2_2") (pintype "passive"))
      (node (ref "C18") (pin "1") (pinfunction "1_1") (pintype "passive"))
      (node (ref "C20") (pin "2") (pinfunction "2_2") (pintype "passive"))
      (node (ref "C22") (pin "1") (pinfunction "1_1") (pintype "passive"))
      (node (ref "C26") (pin "1") (pinfunction "1_1") (pintype "passive"))
      (node (ref "C27") (pin "1") (pinfunction "1_1") (pintype "passive"))
      (node (ref "C28") (pin "1") (pinfunction "1_1") (pintype "passive"))
      (node (ref "C29") (pin "1") (pinfunction "1_1") (pintype "passive"))
      (node (ref "C30") (pin "1") (pinfunction "1_1") (pintype "passive"))
      (node (ref "C31") (pin "1") (pinfunction "1_1") (pintype "passive"))
      (node (ref "C32") (pin "1") (pinfunction "1_1") (pintype "passive"))
      (node (ref "C33") (pin "1") (pinfunction "1_1") (pintype "passive"))
      (node (ref "C34") (pin "1") (pinfunction "1_1") (pintype "passive"))
      (node (ref "C35") (pin "1") (pinfunction "1_1") (pintype "passive"))
      (node (ref "C37") (pin "1") (pinfunction "1_1") (pintype "passive"))
      (node (ref "C38") (pin "1") (pinfunction "1_1") (pintype "passive"))
      (node (ref "C39") (pin "1") (pinfunction "1_1") (pintype "passive"))
      (node (ref "C40") (pin "1") (pinfunction "1_1") (pintype "passive"))
      (node (ref "C41") (pin "1") (pinfunction "1_1") (pintype "passive"))
      (node (ref "C42") (pin "1") (pinfunction "1_1") (pintype "passive"))
      (node (ref "C43") (pin "1") (pinfunction "1_1") (pintype "passive"))
      (node (ref "C44") (pin "1") (pinfunction "1_1") (pintype "passive"))
      (node (ref "C45") (pin "1") (pinfunction "1_1") (pintype "passive"))
      (node (ref "C46") (pin "1") (pinfunction "1_1") (pintype "passive"))
      (node (ref "C47") (pin "2") (pinfunction "2_2") (pintype "passive"))
      (node (ref "C48") (pin "2") (pinfunction "2_2") (pintype "passive"))
      (node (ref "C49") (pin "2") (pinfunction "2_2") (pintype "passive"))
      (node (ref "C6") (pin "2") (pinfunction "2_2") (pintype "passive"))
      (node (ref "C8") (pin "1") (pinfunction "1_1") (pintype "passive"))
      (node (ref "R17") (pin "1") (pinfunction "1_1") (pintype "passive"))
      (node (ref "R18") (pin "1") (pinfunction "1_1") (pintype "passive"))
      (node (ref "R22") (pin "1") (pinfunction "1_1") (pintype "passive"))
      (node (ref "R23") (pin "1") (pinfunction "1_1") (pintype "passive"))
      (node (ref "R24") (pin "1") (pinfunction "1_1") (pintype "passive"))
      (node (ref "R27") (pin "1") (pinfunction "1_1") (pintype "passive"))
      (node (ref "R30") (pin "1") (pinfunction "1_1") (pintype "passive"))
      (node (ref "R41") (pin "2") (pinfunction "2_2") (pintype "passive"))
      (node (ref "U1") (pin "57") (pinfunction "GND_(EP)_57") (pintype "power_in"))
      (node (ref "U2") (pin "17") (pinfunction "Exposed_pad_17") (pintype "passive"))
      (node (ref "U2") (pin "3") (pinfunction "GND_3") (pintype "power_in"))
      (node (ref "Y1") (pin "2") (pinfunction "GND_2") (pintype "power_in"))
      (node (ref "Y1") (pin "4") (pinfunction "GND_4") (pintype "power_in"))
    )
    (net (code "54") (name "Net-(C6-Pad1)") (class "Default")
      (node (ref "C6") (pin "1") (pinfunction "1_1") (pintype "passive"))
      (node (ref "L1") (pin "2") (pinfunction "2_2") (pintype "passive"))
      (node (ref "L2") (pin "1") (pinfunction "1_1") (pintype "passive"))
      (node (ref "R16") (pin "2") (pinfunction "2_2") (pintype "passive"))
    )
    (net (code "55") (name "Net-(C7-Pad2)") (class "Default")
      (node (ref "C7") (pin "2") (pinfunction "2_2") (pintype "passive"))
      (node (ref "R18") (pin "2") (pinfunction "2_2") (pintype "passive"))
    )
    (net (code "56") (name "Net-(C10-Pad1)") (class "Default")
      (node (ref "C10") (pin "1") (pinfunction "1_1") (pintype "passive"))
      (node (ref "L4") (pin "2") (pinfunction "2_2") (pintype "passive"))
      (node (ref "L5") (pin "1") (pinfunction "1_1") (pintype "passive"))
      (node (ref "R21") (pin "2") (pinfunction "2_2") (pintype "passive"))
    )
    (net (code "57") (name "Net-(C11-Pad2)") (class "Default")
      (node (ref "C11") (pin "2") (pinfunction "2_2") (pintype "passive"))
      (node (ref "R24") (pin "2") (pinfunction "2_2") (pintype "passive"))
    )
    (net (code "58") (name "Net-(C16-Pad1)") (class "Default")
      (node (ref "C16") (pin "1") (pinfunction "1_1") (pintype "passive"))
      (node (ref "L7") (pin "2") (pinfunction "2_2") (pintype "passive"))
      (node (ref "L8") (pin "1") (pinfunction "1_1") (pintype "passive"))
      (node (ref "R26") (pin "2") (pinfunction "2_2") (pintype "passive"))
    )
    (net (code "59") (name "Net-(C17-Pad2)") (class "Default")
      (node (ref "C17") (pin "2") (pinfunction "2_2") (pintype "passive"))
      (node (ref "R27") (pin "2") (pinfunction "2_2") (pintype "passive"))
    )
    (net (code "60") (name "Net-(C20-Pad1)") (class "Default")
      (node (ref "C20") (pin "1") (pinfunction "1_1") (pintype "passive"))
      (node (ref "L10") (pin "2") (pinfunction "2_2") (pintype "passive"))
      (node (ref "L11") (pin "1") (pinfunction "1_1") (pintype "passive"))
      (node (ref "R29") (pin "2") (pinfunction "2_2") (pintype "passive"))
    )
    (net (code "61") (name "Net-(C21-Pad2)") (class "Default")
      (node (ref "C21") (pin "2") (pinfunction "2_2") (pintype "passive"))
      (node (ref "R30") (pin "2") (pinfunction "2_2") (pintype "passive"))
    )
    (net (code "62") (name "Net-(C28-Pad2)") (class "Default")
      (node (ref "C28") (pin "2") (pinfunction "2_2") (pintype "passive"))
      (node (ref "C29") (pin "2") (pinfunction "2_2") (pintype "passive"))
      (node (ref "C30") (pin "2") (pinfunction "2_2") (pintype "passive"))
      (node (ref "U1") (pin "8") (pinfunction "CAP_VDD_8") (pintype "power_in"))
    )
    (net (code "63") (name "Net-(C31-Pad2)") (class "Default")
      (node (ref "C31") (pin "2") (pinfunction "2_2") (pintype "passive"))
      (node (ref "C32") (pin "2") (pinfunction "2_2") (pintype "passive"))
      (node (ref "C33") (pin "2") (pinfunction "2_2") (pintype "passive"))
      (node (ref "U1") (pin "20") (pinfunction "CAP_VDD_20") (pintype "power_in"))
    )
    (net (code "64") (name "Net-(L2-Pad2)") (class "Default")
      (node (ref "L2") (pin "2") (pinfunction "2_2") (pintype "passive"))
      (node (ref "L3") (pin "1") (pinfunction "1_1") (pintype "passive"))
      (node (ref "R16") (pin "1") (pinfunction "1_1") (pintype "passive"))
    )
    (net (code "65") (name "Net-(L5-Pad2)") (class "Default")
      (node (ref "L5") (pin "2") (pinfunction "2_2") (pintype "passive"))
      (node (ref "L6") (pin "1") (pinfunction "1_1") (pintype "passive"))
      (node (ref "R21") (pin "1") (pinfunction "1_1") (pintype "passive"))
    )
    (net (code "66") (name "Net-(L8-Pad2)") (class "Default")
      (node (ref "L8") (pin "2") (pinfunction "2_2") (pintype "passive"))
      (node (ref "L9") (pin "1") (pinfunction "1_1") (pintype "passive"))
      (node (ref "R26") (pin "1") (pinfunction "1_1") (pintype "passive"))
    )
    (net (code "67") (name "Net-(L11-Pad2)") (class "Default")
      (node (ref "L11") (pin "2") (pinfunction "2_2") (pintype "passive"))
      (node (ref "L12") (pin "1") (pinfunction "1_1") (pintype "passive"))
      (node (ref "R29") (pin "1") (pinfunction "1_1") (pintype "passive"))
    )
    (net (code "68") (name "Net-(U1A-XRES)") (class "Default")
      (node (ref "R22") (pin "2") (pinfunction "2_2") (pintype "passive"))
      (node (ref "U1") (pin "17") (pinfunction "XRES_17") (pintype "passive"))
    )
    (net (code "69") (name "Net-(U2-ADDRSEL)") (class "Default")
      (node (ref "R41") (pin "1") (pinfunction "1_1") (pintype "passive"))
      (node (ref "U2") (pin "6") (pinfunction "ADDRSEL_6") (pintype "input"))
    )
    (net (code "70") (name "Net-(U2-SENSE1+)") (class "Default")
      (node (ref "C23") (pin "2") (pinfunction "2_2") (pintype "passive"))
      (node (ref "R31") (pin "2") (pinfunction "2_2") (pintype "passive"))
      (node (ref "U2") (pin "11") (pinfunction "SENSE1+_11") (pintype "passive"))
    )
    (net (code "71") (name "Net-(U2-SENSE1-)") (class "Default")
      (node (ref "C23") (pin "1") (pinfunction "1_1") (pintype "passive"))
      (node (ref "R32") (pin "2") (pinfunction "2_2") (pintype "passive"))
      (node (ref "U2") (pin "12") (pinfunction "SENSE1-_12") (pintype "passive"))
    )
    (net (code "72") (name "Net-(U2-SENSE2+)") (class "Default")
      (node (ref "C24") (pin "2") (pinfunction "2_2") (pintype "passive"))
      (node (ref "R33") (pin "2") (pinfunction "2_2") (pintype "passive"))
      (node (ref "U2") (pin "13") (pinfunction "SENSE2+_13") (pintype "passive"))
    )
    (net (code "73") (name "Net-(U2-SENSE2-)") (class "Default")
      (node (ref "C24") (pin "1") (pinfunction "1_1") (pintype "passive"))
      (node (ref "R34") (pin "2") (pinfunction "2_2") (pintype "passive"))
      (node (ref "U2") (pin "14") (pinfunction "SENSE2-_14") (pintype "passive"))
    )
    (net (code "74") (name "Net-(U2-SENSE3+)") (class "Default")
      (node (ref "C25") (pin "2") (pinfunction "2_2") (pintype "passive"))
      (node (ref "R35") (pin "2") (pinfunction "2_2") (pintype "passive"))
      (node (ref "U2") (pin "8") (pinfunction "SENSE3+_8") (pintype "passive"))
    )
    (net (code "75") (name "Net-(U2-SENSE3-)") (class "Default")
      (node (ref "C25") (pin "1") (pinfunction "1_1") (pintype "passive"))
      (node (ref "R36") (pin "2") (pinfunction "2_2") (pintype "passive"))
      (node (ref "U2") (pin "7") (pinfunction "SENSE3-_7") (pintype "passive"))
    )
    (net (code "76") (name "Net-(U2-SENSE4+)") (class "Default")
      (node (ref "C36") (pin "2") (pinfunction "2_2") (pintype "passive"))
      (node (ref "R38") (pin "2") (pinfunction "2_2") (pintype "passive"))
      (node (ref "U2") (pin "10") (pinfunction "SENSE4+_10") (pintype "passive"))
    )
    (net (code "77") (name "Net-(U2-SENSE4-)") (class "Default")
      (node (ref "C36") (pin "1") (pinfunction "1_1") (pintype "passive"))
      (node (ref "R40") (pin "2") (pinfunction "2_2") (pintype "passive"))
      (node (ref "U2") (pin "9") (pinfunction "SENSE4-_9") (pintype "passive"))
    )
    (net (code "78") (name "Net-(U2-~{PWRDN})") (class "Default")
      (node (ref "R37") (pin "1") (pinfunction "1_1") (pintype "passive"))
      (node (ref "U2") (pin "16") (pinfunction "~{PWRDN}_16") (pintype "input"))
    )
    (net (code "79") (name "unconnected-(U1A-CKCN-Pad34)") (class "Default")
      (node (ref "U1") (pin "34") (pinfunction "CKCN_34") (pintype "bidirectional+no_connect"))
    )
    (net (code "80") (name "unconnected-(U1A-CKCP-Pad33)") (class "Default")
      (node (ref "U1") (pin "33") (pinfunction "CKCP_33") (pintype "bidirectional+no_connect"))
    )
    (net (code "81") (name "unconnected-(U1B-NC{slash}CKBN-Pad46)") (class "Default")
      (node (ref "U1") (pin "46") (pinfunction "NC/CKBN_46") (pintype "passive+no_connect"))
    )
    (net (code "82") (name "unconnected-(U1B-NC{slash}CKBP-Pad45)") (class "Default")
      (node (ref "U1") (pin "45") (pinfunction "NC/CKBP_45") (pintype "passive+no_connect"))
    )
    (net (code "83") (name "unconnected-(U1B-NC{slash}CKFN-Pad52)") (class "Default")
      (node (ref "U1") (pin "52") (pinfunction "NC/CKFN_52") (pintype "passive+no_connect"))
    )
    (net (code "84") (name "unconnected-(U1B-NC{slash}CKFP-Pad51)") (class "Default")
      (node (ref "U1") (pin "51") (pinfunction "NC/CKFP_51") (pintype "passive+no_connect"))
    )
    (net (code "85") (name "unconnected-(U1B-NC{slash}DB0N-Pad44)") (class "Default")
      (node (ref "U1") (pin "44") (pinfunction "NC/DB0N_44") (pintype "passive+no_connect"))
    )
    (net (code "86") (name "unconnected-(U1B-NC{slash}DB0P-Pad43)") (class "Default")
      (node (ref "U1") (pin "43") (pinfunction "NC/DB0P_43") (pintype "passive+no_connect"))
    )
    (net (code "87") (name "unconnected-(U1B-NC{slash}DB1N-Pad48)") (class "Default")
      (node (ref "U1") (pin "48") (pinfunction "NC/DB1N_48") (pintype "passive+no_connect"))
    )
    (net (code "88") (name "unconnected-(U1B-NC{slash}DB1P-Pad47)") (class "Default")
      (node (ref "U1") (pin "47") (pinfunction "NC/DB1P_47") (pintype "passive+no_connect"))
    )
    (net (code "89") (name "unconnected-(U1B-NC{slash}DB2N-Pad50)") (class "Default")
      (node (ref "U1") (pin "50") (pinfunction "NC/DB2N_50") (pintype "passive+no_connect"))
    )
    (net (code "90") (name "unconnected-(U1B-NC{slash}DB2P-Pad49)") (class "Default")
      (node (ref "U1") (pin "49") (pinfunction "NC/DB2P_49") (pintype "passive+no_connect"))
    )
    (net (code "91") (name "unconnected-(U1B-NC{slash}DB3N-Pad54)") (class "Default")
      (node (ref "U1") (pin "54") (pinfunction "NC/DB3N_54") (pintype "passive+no_connect"))
    )
    (net (code "92") (name "unconnected-(U1B-NC{slash}DB3P-Pad53)") (class "Default")
      (node (ref "U1") (pin "53") (pinfunction "NC/DB3P_53") (pintype "passive+no_connect"))
    )
  )
)
